# Temperature_Sensors.net
KiCad netlist of a schematic drawn in Altium Designer
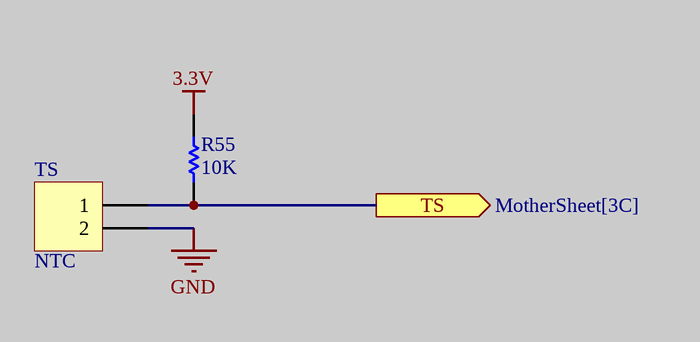
[diagram p0: Temperature Sensors.SchDoc]

(export (version "E")
  (design (tool "Eeschema 10.0.6"))
  (components
    (comp (ref "R55")
      (value "10K")
      (footprint "RESC0603")
      (description "0603,0.1W")
      (fields (field (name "PUBLISHER") "Altium Limited"))
      (libsource (lib "eLIB") (part "Resistor"))
    )
    (comp (ref "TS")
      (value "NTC")
      (footprint "HEADER1*2 xn")
      (description "Header, 2-Pin XN")
      (libsource (lib "SINA") (part "Header1*2 XN"))
    )
  )
  (nets
    (net (code "1") (name "/TS") (class "Default")
      (node (ref "R55") (pin "1") (pinfunction "1_1") (pintype "passive"))
      (node (ref "TS") (pin "1") (pinfunction "1_1") (pintype "passive"))
    )
    (net (code "2") (name "3.3V") (class "Default")
      (node (ref "R55") (pin "2") (pinfunction "2_2") (pintype "passive"))
    )
    (net (code "3") (name "GND") (class "Default")
      (node (ref "TS") (pin "2") (pinfunction "2_2") (pintype "passive"))
    )
  )
)
